# TOP.net
KiCad netlist of a schematic drawn in Altium Designer
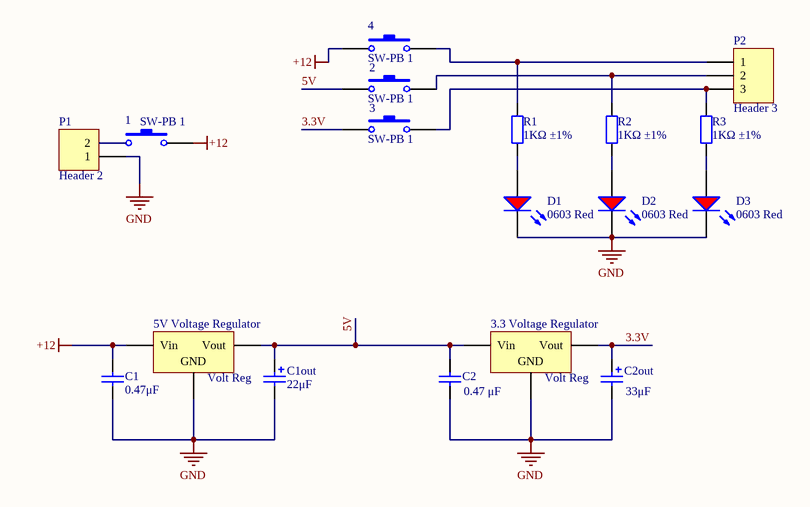
[diagram p0: TOP.SchDoc]

(export (version "E")
  (design (tool "Eeschema 10.0.6"))
  (components
    (comp (ref "1")
      (value "SW-PB 1")
      (footprint "SPST-2")
      (description "Switch")
      (fields (field (name "PUBLISHER") "Altium Limited"))
      (libsource (lib "Miscellaneous Devices") (part "SW-PB"))
    )
    (comp (ref "2")
      (value "SW-PB 1")
      (footprint "SPST-2")
      (description "Switch")
      (fields (field (name "PUBLISHER") "Altium Limited"))
      (libsource (lib "Miscellaneous Devices") (part "SW-PB"))
    )
    (comp (ref "3")
      (value "SW-PB 1")
      (footprint "SPST-2")
      (description "Switch")
      (fields (field (name "PUBLISHER") "Altium Limited"))
      (libsource (lib "Miscellaneous Devices") (part "SW-PB"))
    )
    (comp (ref "3.3 Voltage Regulator")
      (value "Volt Reg")
      (footprint "D2PAK_N")
      (description "Voltage Regulator")
      (fields (field (name "PUBLISHER") "Altium Limited"))
      (libsource (lib "Miscellaneous Devices") (part "Volt Reg"))
    )
    (comp (ref "4")
      (value "SW-PB 1")
      (footprint "SPST-2")
      (description "Switch")
      (fields (field (name "PUBLISHER") "Altium Limited"))
      (libsource (lib "Miscellaneous Devices") (part "SW-PB"))
    )
    (comp (ref "5V Voltage Regulator")
      (value "Volt Reg")
      (footprint "D2PAK_N")
      (description "Voltage Regulator")
      (fields (field (name "PUBLISHER") "Altium Limited"))
      (libsource (lib "Miscellaneous Devices") (part "Volt Reg"))
    )
    (comp (ref "C1")
      (value "0.47μF")
      (footprint "RAD-0.3")
      (description "Capacitor")
      (fields (field (name "PUBLISHER") "Altium Limited"))
      (libsource (lib "Miscellaneous Devices") (part "Cap"))
    )
    (comp (ref "C1out")
      (value "22μF")
      (footprint "POLAR0.8")
      (description "Polarized Capacitor (Axial)")
      (fields (field (name "PUBLISHER") "Altium Limited"))
      (libsource (lib "Miscellaneous Devices") (part "Cap Pol2"))
    )
    (comp (ref "C2")
      (value "0.47 μF")
      (footprint "RAD-0.3")
      (description "Capacitor")
      (fields (field (name "PUBLISHER") "Altium Limited"))
      (libsource (lib "Miscellaneous Devices") (part "Cap"))
    )
    (comp (ref "C2out")
      (value "33μF")
      (footprint "POLAR0.8")
      (description "Polarized Capacitor (Axial)")
      (fields (field (name "PUBLISHER") "Altium Limited"))
      (libsource (lib "Miscellaneous Devices") (part "Cap Pol2"))
    )
    (comp (ref "D1")
      (value "0603 Red")
      (footprint "0603_LED_S1")
      (description "LED")
      (libsource (lib "LED") (part "0603 LED Red"))
    )
    (comp (ref "D2")
      (value "0603 Red")
      (footprint "0603_LED_S1")
      (description "LED")
      (libsource (lib "LED") (part "0603 LED Red"))
    )
    (comp (ref "D3")
      (value "0603 Red")
      (footprint "0603_LED_S1")
      (description "LED")
      (libsource (lib "LED") (part "0603 LED Red"))
    )
    (comp (ref "P1")
      (value "Header 2")
      (footprint "HDR1X2")
      (description "Header, 2-Pin")
      (fields (field (name "PUBLISHER") "Altium Limited"))
      (libsource (lib "Miscellaneous Connectors") (part "Header 2"))
    )
    (comp (ref "P2")
      (value "Header 3")
      (footprint "HDR1X3")
      (description "Header, 3-Pin")
      (fields (field (name "PUBLISHER") "Altium Limited"))
      (libsource (lib "Miscellaneous Connectors") (part "Header 3"))
    )
    (comp (ref "R1")
      (value "1KΩ ±1%")
      (footprint "0402_R")
      (description "Chip resistor")
      (fields (field (name "MANUFACTURER") "Uniroyal Elec") (field (name "PARTNUMBER") "0402WGF1001TCE"))
      (libsource (lib "RES") (part "0402 1K (1001) 1%"))
    )
    (comp (ref "R2")
      (value "1KΩ ±1%")
      (footprint "0402_R")
      (description "Chip resistor")
      (fields (field (name "MANUFACTURER") "Uniroyal Elec") (field (name "PARTNUMBER") "0402WGF1001TCE"))
      (libsource (lib "RES") (part "0402 1K (1001) 1%"))
    )
    (comp (ref "R3")
      (value "1KΩ ±1%")
      (footprint "0402_R")
      (description "Chip resistor")
      (fields (field (name "MANUFACTURER") "Uniroyal Elec") (field (name "PARTNUMBER") "0402WGF1001TCE"))
      (libsource (lib "RES") (part "0402 1K (1001) 1%"))
    )
  )
  (nets
    (net (code "1") (name "+12") (class "Default")
      (node (ref "1") (pin "2") (pinfunction "2_2") (pintype "passive"))
      (node (ref "4") (pin "1") (pinfunction "1_1") (pintype "passive"))
      (node (ref "5V Voltage Regulator") (pin "1") (pinfunction "Vin_1") (pintype "passive"))
      (node (ref "C1") (pin "2") (pinfunction "2_2") (pintype "passive"))
    )
    (net (code "2") (name "/3.3V") (class "Default")
      (node (ref "3") (pin "1") (pinfunction "1_1") (pintype "passive"))
      (node (ref "3.3 Voltage Regulator") (pin "3") (pinfunction "Vout_3") (pintype "passive"))
      (node (ref "C2out") (pin "1") (pinfunction "1_1") (pintype "passive"))
    )
    (net (code "3") (name "/5V") (class "Default")
      (node (ref "2") (pin "1") (pinfunction "1_1") (pintype "passive"))
      (node (ref "3.3 Voltage Regulator") (pin "1") (pinfunction "Vin_1") (pintype "passive"))
      (node (ref "5V Voltage Regulator") (pin "3") (pinfunction "Vout_3") (pintype "passive"))
      (node (ref "C1out") (pin "1") (pinfunction "1_1") (pintype "passive"))
      (node (ref "C2") (pin "2") (pinfunction "2_2") (pintype "passive"))
    )
    (net (code "4") (name "GND") (class "Default")
      (node (ref "3.3 Voltage Regulator") (pin "2") (pinfunction "GND_2") (pintype "passive"))
      (node (ref "5V Voltage Regulator") (pin "2") (pinfunction "GND_2") (pintype "passive"))
      (node (ref "C1") (pin "1") (pinfunction "1_1") (pintype "passive"))
      (node (ref "C1out") (pin "2") (pinfunction "2_2") (pintype "passive"))
      (node (ref "C2") (pin "1") (pinfunction "1_1") (pintype "passive"))
      (node (ref "C2out") (pin "2") (pinfunction "2_2") (pintype "passive"))
      (node (ref "D1") (pin "K") (pinfunction "K_K") (pintype "passive"))
      (node (ref "D2") (pin "K") (pinfunction "K_K") (pintype "passive"))
      (node (ref "D3") (pin "K") (pinfunction "K_K") (pintype "passive"))
      (node (ref "P1") (pin "1") (pinfunction "1_1") (pintype "passive"))
    )
    (net (code "5") (name "Net-(1-Pad1)") (class "Default")
      (node (ref "1") (pin "1") (pinfunction "1_1") (pintype "passive"))
      (node (ref "P1") (pin "2") (pinfunction "2_2") (pintype "passive"))
    )
    (net (code "6") (name "Net-(2-Pad2)") (class "Default")
      (node (ref "2") (pin "2") (pinfunction "2_2") (pintype "passive"))
      (node (ref "P2") (pin "2") (pinfunction "2_2") (pintype "passive"))
      (node (ref "R2") (pin "2") (pinfunction "2_2") (pintype "passive"))
    )
    (net (code "7") (name "Net-(3-Pad2)") (class "Default")
      (node (ref "3") (pin "2") (pinfunction "2_2") (pintype "passive"))
      (node (ref "P2") (pin "3") (pinfunction "3_3") (pintype "passive"))
      (node (ref "R3") (pin "2") (pinfunction "2_2") (pintype "passive"))
    )
    (net (code "8") (name "Net-(4-Pad2)") (class "Default")
      (node (ref "4") (pin "2") (pinfunction "2_2") (pintype "passive"))
      (node (ref "P2") (pin "1") (pinfunction "1_1") (pintype "passive"))
      (node (ref "R1") (pin "2") (pinfunction "2_2") (pintype "passive"))
    )
    (net (code "9") (name "Net-(D1-PadA)") (class "Default")
      (node (ref "D1") (pin "A") (pinfunction "A_A") (pintype "passive"))
      (node (ref "R1") (pin "1") (pinfunction "1_1") (pintype "passive"))
    )
    (net (code "10") (name "Net-(D2-PadA)") (class "Default")
      (node (ref "D2") (pin "A") (pinfunction "A_A") (pintype "passive"))
      (node (ref "R2") (pin "1") (pinfunction "1_1") (pintype "passive"))
    )
    (net (code "11") (name "Net-(D3-PadA)") (class "Default")
      (node (ref "D3") (pin "A") (pinfunction "A_A") (pintype "passive"))
      (node (ref "R3") (pin "1") (pinfunction "1_1") (pintype "passive"))
    )
  )
)
